# schematic.net
KiCad netlist of a schematic drawn in EAGLE
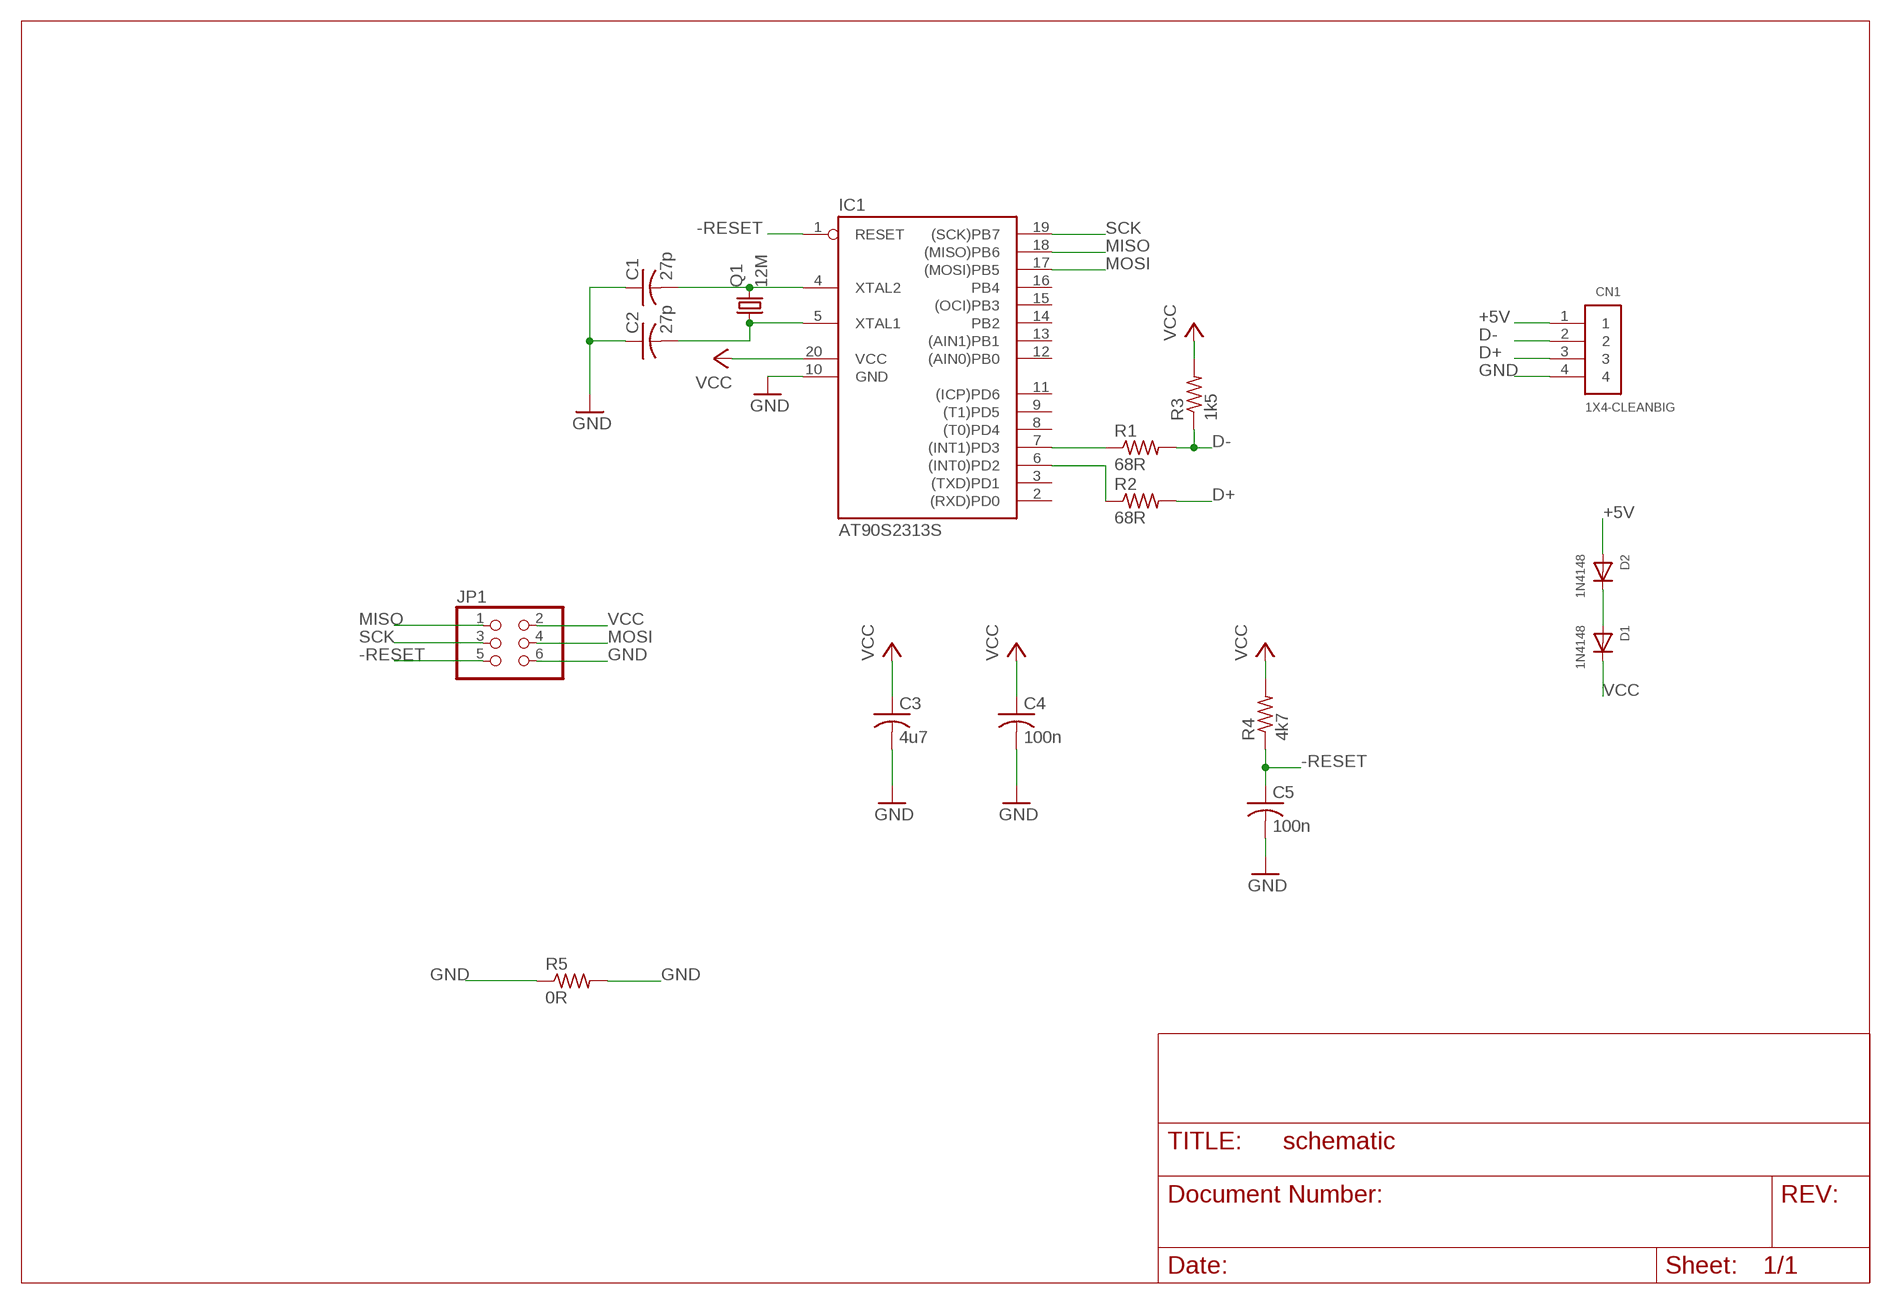
[diagram p0: schematic, sheet 1]

(export (version "E")
  (design (tool "Eeschema 10.0.6"))
  (components
    (comp (ref "C1")
      (value "27p")
      (footprint "eagle-import:C0805")
      (libsource (lib "eagle-import") (part "C-USC0805"))
    )
    (comp (ref "C2")
      (value "27p")
      (footprint "eagle-import:C0805")
      (libsource (lib "eagle-import") (part "C-USC0805"))
    )
    (comp (ref "C3")
      (value "4u7")
      (footprint "eagle-import:C0805")
      (libsource (lib "eagle-import") (part "C-USC0805"))
    )
    (comp (ref "C4")
      (value "100n")
      (footprint "eagle-import:C0805")
      (libsource (lib "eagle-import") (part "C-USC0805"))
    )
    (comp (ref "C5")
      (value "100n")
      (footprint "eagle-import:C0805")
      (libsource (lib "eagle-import") (part "C-USC0805"))
    )
    (comp (ref "CN1")
      (value "1X4-CLEANBIG")
      (footprint "eagle-import:1X04-CLEANBIG")
      (libsource (lib "eagle-import") (part "1X4-CLEANBIG"))
    )
    (comp (ref "D1")
      (value "1N4148")
      (footprint "eagle-import:SMADIODE")
      (libsource (lib "eagle-import") (part "DIODESMA"))
    )
    (comp (ref "D2")
      (value "1N4148")
      (footprint "eagle-import:SMADIODE")
      (libsource (lib "eagle-import") (part "DIODESMA"))
    )
    (comp (ref "IC1")
      (value "AT90S2313S")
      (footprint "eagle-import:SO20L")
      (libsource (lib "eagle-import") (part "AT90S2313S"))
    )
    (comp (ref "JP1")
      (value "PINHD-2X3")
      (footprint "eagle-import:2X03")
      (libsource (lib "eagle-import") (part "PINHD-2X3"))
    )
    (comp (ref "Q1")
      (value "12M")
      (footprint "eagle-import:HC49UP")
      (libsource (lib "eagle-import") (part "CRYSTALHC49UP"))
    )
    (comp (ref "R1")
      (value "68R")
      (footprint "eagle-import:R0805")
      (libsource (lib "eagle-import") (part "R-US_R0805"))
    )
    (comp (ref "R2")
      (value "68R")
      (footprint "eagle-import:R0805")
      (libsource (lib "eagle-import") (part "R-US_R0805"))
    )
    (comp (ref "R3")
      (value "1k5")
      (footprint "eagle-import:R0805")
      (libsource (lib "eagle-import") (part "R-US_R0805"))
    )
    (comp (ref "R4")
      (value "4k7")
      (footprint "eagle-import:R0805")
      (libsource (lib "eagle-import") (part "R-US_R0805"))
    )
    (comp (ref "R5")
      (value "0R")
      (footprint "eagle-import:R1206")
      (libsource (lib "eagle-import") (part "R-US_R1206"))
    )
  )
  (nets
    (net (code "1") (name "/+5V") (class "Default")
      (node (ref "CN1") (pin "1") (pinfunction "1_1") (pintype "bidirectional"))
      (node (ref "D2") (pin "A") (pinfunction "A_A") (pintype "passive"))
    )
    (net (code "2") (name "/-RESET") (class "Default")
      (node (ref "C5") (pin "1") (pinfunction "1_1") (pintype "passive"))
      (node (ref "IC1") (pin "1") (pinfunction "RESET_1") (pintype "bidirectional"))
      (node (ref "JP1") (pin "5") (pinfunction "5_5") (pintype "passive"))
      (node (ref "R4") (pin "1") (pinfunction "1_1") (pintype "passive"))
    )
    (net (code "3") (name "/D+") (class "Default")
      (node (ref "CN1") (pin "3") (pinfunction "3_3") (pintype "bidirectional"))
      (node (ref "R2") (pin "2") (pinfunction "2_2") (pintype "passive"))
    )
    (net (code "4") (name "/D-") (class "Default")
      (node (ref "CN1") (pin "2") (pinfunction "2_2") (pintype "bidirectional"))
      (node (ref "R1") (pin "2") (pinfunction "2_2") (pintype "passive"))
      (node (ref "R3") (pin "1") (pinfunction "1_1") (pintype "passive"))
    )
    (net (code "5") (name "/MISO") (class "Default")
      (node (ref "IC1") (pin "18") (pinfunction "(MISO)PB6_18") (pintype "bidirectional"))
      (node (ref "JP1") (pin "1") (pinfunction "1_1") (pintype "passive"))
    )
    (net (code "6") (name "/MOSI") (class "Default")
      (node (ref "IC1") (pin "17") (pinfunction "(MOSI)PB5_17") (pintype "bidirectional"))
      (node (ref "JP1") (pin "4") (pinfunction "4_4") (pintype "passive"))
    )
    (net (code "7") (name "/SCK") (class "Default")
      (node (ref "IC1") (pin "19") (pinfunction "(SCK)PB7_19") (pintype "bidirectional"))
      (node (ref "JP1") (pin "3") (pinfunction "3_3") (pintype "passive"))
    )
    (net (code "8") (name "GND") (class "Default")
      (node (ref "C1") (pin "1") (pinfunction "1_1") (pintype "passive"))
      (node (ref "C2") (pin "1") (pinfunction "1_1") (pintype "passive"))
      (node (ref "C3") (pin "2") (pinfunction "2_2") (pintype "passive"))
      (node (ref "C4") (pin "2") (pinfunction "2_2") (pintype "passive"))
      (node (ref "C5") (pin "2") (pinfunction "2_2") (pintype "passive"))
      (node (ref "CN1") (pin "4") (pinfunction "4_4") (pintype "bidirectional"))
      (node (ref "IC1") (pin "10") (pinfunction "GND_10") (pintype "power_in"))
      (node (ref "JP1") (pin "6") (pinfunction "6_6") (pintype "passive"))
      (node (ref "R5") (pin "1") (pinfunction "1_1") (pintype "passive"))
      (node (ref "R5") (pin "2") (pinfunction "2_2") (pintype "passive"))
    )
    (net (code "9") (name "Net-(D1-PadA)") (class "Default")
      (node (ref "D1") (pin "A") (pinfunction "A_A") (pintype "passive"))
      (node (ref "D2") (pin "C") (pinfunction "C_C") (pintype "passive"))
    )
    (net (code "10") (name "Net-(IC1-(INT0)PD2)") (class "Default")
      (node (ref "IC1") (pin "6") (pinfunction "(INT0)PD2_6") (pintype "bidirectional"))
      (node (ref "R2") (pin "1") (pinfunction "1_1") (pintype "passive"))
    )
    (net (code "11") (name "Net-(IC1-(INT1)PD3)") (class "Default")
      (node (ref "IC1") (pin "7") (pinfunction "(INT1)PD3_7") (pintype "bidirectional"))
      (node (ref "R1") (pin "1") (pinfunction "1_1") (pintype "passive"))
    )
    (net (code "12") (name "Net-(IC1-XTAL1)") (class "Default")
      (node (ref "C2") (pin "2") (pinfunction "2_2") (pintype "passive"))
      (node (ref "IC1") (pin "5") (pinfunction "XTAL1_5") (pintype "bidirectional"))
      (node (ref "Q1") (pin "1") (pinfunction "1_1") (pintype "passive"))
    )
    (net (code "13") (name "Net-(IC1-XTAL2)") (class "Default")
      (node (ref "C1") (pin "2") (pinfunction "2_2") (pintype "passive"))
      (node (ref "IC1") (pin "4") (pinfunction "XTAL2_4") (pintype "bidirectional"))
      (node (ref "Q1") (pin "2") (pinfunction "2_2") (pintype "passive"))
    )
    (net (code "14") (name "VCC") (class "Default")
      (node (ref "C3") (pin "1") (pinfunction "1_1") (pintype "passive"))
      (node (ref "C4") (pin "1") (pinfunction "1_1") (pintype "passive"))
      (node (ref "D1") (pin "C") (pinfunction "C_C") (pintype "passive"))
      (node (ref "IC1") (pin "20") (pinfunction "VCC_20") (pintype "power_in"))
      (node (ref "JP1") (pin "2") (pinfunction "2_2") (pintype "passive"))
      (node (ref "R3") (pin "2") (pinfunction "2_2") (pintype "passive"))
      (node (ref "R4") (pin "2") (pinfunction "2_2") (pintype "passive"))
    )
    (net (code "15") (name "unconnected-(IC1-(AIN0)PB0-Pad12)") (class "Default")
      (node (ref "IC1") (pin "12") (pinfunction "(AIN0)PB0_12") (pintype "bidirectional"))
    )
    (net (code "16") (name "unconnected-(IC1-(AIN1)PB1-Pad13)") (class "Default")
      (node (ref "IC1") (pin "13") (pinfunction "(AIN1)PB1_13") (pintype "bidirectional"))
    )
    (net (code "17") (name "unconnected-(IC1-(ICP)PD6-Pad11)") (class "Default")
      (node (ref "IC1") (pin "11") (pinfunction "(ICP)PD6_11") (pintype "bidirectional"))
    )
    (net (code "18") (name "unconnected-(IC1-(OCI)PB3-Pad15)") (class "Default")
      (node (ref "IC1") (pin "15") (pinfunction "(OCI)PB3_15") (pintype "bidirectional"))
    )
    (net (code "19") (name "unconnected-(IC1-(RXD)PD0-Pad2)") (class "Default")
      (node (ref "IC1") (pin "2") (pinfunction "(RXD)PD0_2") (pintype "bidirectional"))
    )
    (net (code "20") (name "unconnected-(IC1-(T0)PD4-Pad8)") (class "Default")
      (node (ref "IC1") (pin "8") (pinfunction "(T0)PD4_8") (pintype "bidirectional"))
    )
    (net (code "21") (name "unconnected-(IC1-(T1)PD5-Pad9)") (class "Default")
      (node (ref "IC1") (pin "9") (pinfunction "(T1)PD5_9") (pintype "bidirectional"))
    )
    (net (code "22") (name "unconnected-(IC1-(TXD)PD1-Pad3)") (class "Default")
      (node (ref "IC1") (pin "3") (pinfunction "(TXD)PD1_3") (pintype "bidirectional"))
    )
    (net (code "23") (name "unconnected-(IC1-PB2-Pad14)") (class "Default")
      (node (ref "IC1") (pin "14") (pinfunction "PB2_14") (pintype "bidirectional"))
    )
    (net (code "24") (name "unconnected-(IC1-PB4-Pad16)") (class "Default")
      (node (ref "IC1") (pin "16") (pinfunction "PB4_16") (pintype "bidirectional"))
    )
  )
)
